# RN4020_Breakout.net
KiCad netlist of a schematic drawn in EAGLE
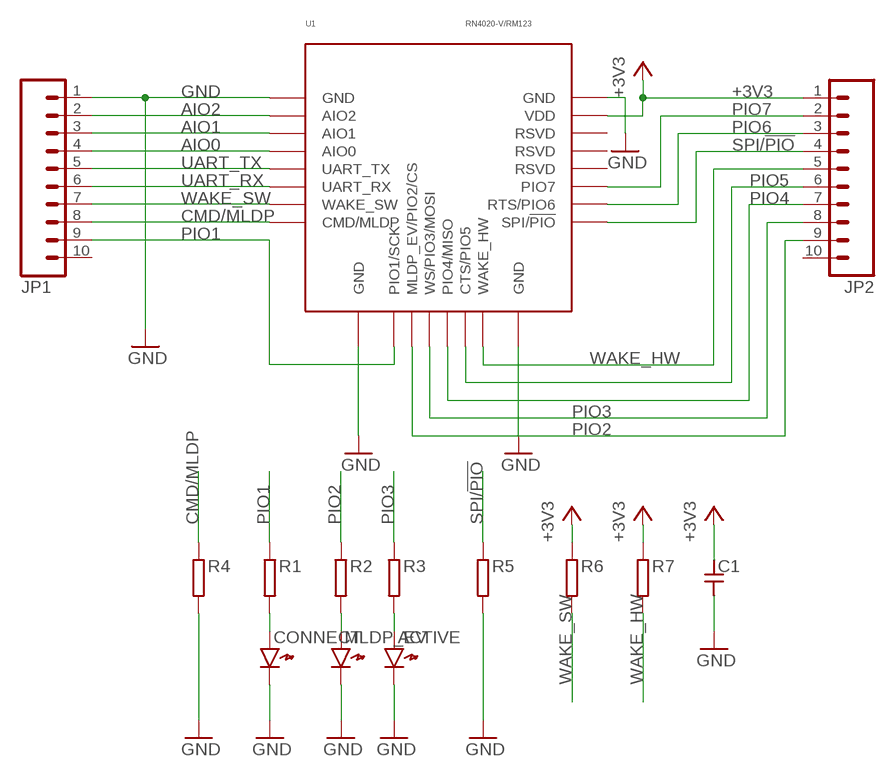
[diagram p0: schematic, sheet 1]

(export (version "E")
  (design (tool "Eeschema 10.0.6"))
  (components
    (comp (ref "ACTIVE")
      (value "LED1608_REDUCED")
      (footprint "eagle-import:LED1608_REDUCED")
      (libsource (lib "eagle-import") (part "LED1608_REDUCED"))
    )
    (comp (ref "C1")
      (value "CAPACITOR1608_REDUCED")
      (footprint "eagle-import:SMD1608_REDUCED")
      (libsource (lib "eagle-import") (part "CAPACITOR1608_REDUCED"))
    )
    (comp (ref "CONNECT")
      (value "LED1608_REDUCED")
      (footprint "eagle-import:LED1608_REDUCED")
      (libsource (lib "eagle-import") (part "LED1608_REDUCED"))
    )
    (comp (ref "JP1")
      (value "M10NOSILK")
      (footprint "eagle-import:1X10-NOSILK")
      (libsource (lib "eagle-import") (part "M10NOSILK"))
    )
    (comp (ref "JP2")
      (value "M10NOSILK")
      (footprint "eagle-import:1X10-NOSILK")
      (libsource (lib "eagle-import") (part "M10NOSILK"))
    )
    (comp (ref "MLDP_EV")
      (value "LED1608_REDUCED")
      (footprint "eagle-import:LED1608_REDUCED")
      (libsource (lib "eagle-import") (part "LED1608_REDUCED"))
    )
    (comp (ref "R1")
      (value "RESISTOR1608_REDUCED")
      (footprint "eagle-import:SMD1608_REDUCED")
      (libsource (lib "eagle-import") (part "RESISTOR1608_REDUCED"))
    )
    (comp (ref "R2")
      (value "RESISTOR1608_REDUCED")
      (footprint "eagle-import:SMD1608_REDUCED")
      (libsource (lib "eagle-import") (part "RESISTOR1608_REDUCED"))
    )
    (comp (ref "R3")
      (value "RESISTOR1608_REDUCED")
      (footprint "eagle-import:SMD1608_REDUCED")
      (libsource (lib "eagle-import") (part "RESISTOR1608_REDUCED"))
    )
    (comp (ref "R4")
      (value "RESISTOR1608_REDUCED")
      (footprint "eagle-import:SMD1608_REDUCED")
      (libsource (lib "eagle-import") (part "RESISTOR1608_REDUCED"))
    )
    (comp (ref "R5")
      (value "RESISTOR1608_REDUCED")
      (footprint "eagle-import:SMD1608_REDUCED")
      (libsource (lib "eagle-import") (part "RESISTOR1608_REDUCED"))
    )
    (comp (ref "R6")
      (value "RESISTOR1608_REDUCED")
      (footprint "eagle-import:SMD1608_REDUCED")
      (libsource (lib "eagle-import") (part "RESISTOR1608_REDUCED"))
    )
    (comp (ref "R7")
      (value "RESISTOR1608_REDUCED")
      (footprint "eagle-import:SMD1608_REDUCED")
      (libsource (lib "eagle-import") (part "RESISTOR1608_REDUCED"))
    )
    (comp (ref "U1")
      (value "RN4020-V/RM123")
      (footprint "eagle-import:RN4020")
      (libsource (lib "eagle-import") (part "RN4020-V/RM123"))
    )
  )
  (nets
    (net (code "1") (name "+3V3") (class "Default")
      (node (ref "C1") (pin "1") (pinfunction "1_1") (pintype "passive"))
      (node (ref "JP2") (pin "1") (pinfunction "1_1") (pintype "passive"))
      (node (ref "R6") (pin "1") (pinfunction "1_1") (pintype "passive"))
      (node (ref "R7") (pin "1") (pinfunction "1_1") (pintype "passive"))
      (node (ref "U1") (pin "23") (pinfunction "VDD_23") (pintype "bidirectional"))
    )
    (net (code "2") (name "/AIO0") (class "Default")
      (node (ref "JP1") (pin "4") (pinfunction "4_4") (pintype "passive"))
      (node (ref "U1") (pin "4") (pinfunction "AIO0_4") (pintype "bidirectional"))
    )
    (net (code "3") (name "/AIO1") (class "Default")
      (node (ref "JP1") (pin "3") (pinfunction "3_3") (pintype "passive"))
      (node (ref "U1") (pin "3") (pinfunction "AIO1_3") (pintype "bidirectional"))
    )
    (net (code "4") (name "/AIO2") (class "Default")
      (node (ref "JP1") (pin "2") (pinfunction "2_2") (pintype "passive"))
      (node (ref "U1") (pin "2") (pinfunction "AIO2_2") (pintype "bidirectional"))
    )
    (net (code "5") (name "/CMD{slash}MLDP") (class "Default")
      (node (ref "JP1") (pin "8") (pinfunction "8_8") (pintype "passive"))
      (node (ref "R4") (pin "1") (pinfunction "1_1") (pintype "passive"))
      (node (ref "U1") (pin "8") (pinfunction "CMD/MLDP_8") (pintype "bidirectional"))
    )
    (net (code "6") (name "/PIO1") (class "Default")
      (node (ref "JP1") (pin "9") (pinfunction "9_9") (pintype "passive"))
      (node (ref "R1") (pin "1") (pinfunction "1_1") (pintype "passive"))
      (node (ref "U1") (pin "10") (pinfunction "PIO1/SCK_10") (pintype "bidirectional"))
    )
    (net (code "7") (name "/PIO2") (class "Default")
      (node (ref "JP2") (pin "9") (pinfunction "9_9") (pintype "passive"))
      (node (ref "R2") (pin "1") (pinfunction "1_1") (pintype "passive"))
      (node (ref "U1") (pin "11") (pinfunction "MLDP_EV/PIO2/CS_11") (pintype "bidirectional"))
    )
    (net (code "8") (name "/PIO3") (class "Default")
      (node (ref "JP2") (pin "8") (pinfunction "8_8") (pintype "passive"))
      (node (ref "R3") (pin "1") (pinfunction "1_1") (pintype "passive"))
      (node (ref "U1") (pin "12") (pinfunction "WS/PIO3/MOSI_12") (pintype "bidirectional"))
    )
    (net (code "9") (name "/PIO4") (class "Default")
      (node (ref "JP2") (pin "7") (pinfunction "7_7") (pintype "passive"))
      (node (ref "U1") (pin "13") (pinfunction "PIO4/MISO_13") (pintype "bidirectional"))
    )
    (net (code "10") (name "/PIO5") (class "Default")
      (node (ref "JP2") (pin "6") (pinfunction "6_6") (pintype "passive"))
      (node (ref "U1") (pin "14") (pinfunction "CTS/PIO5_14") (pintype "bidirectional"))
    )
    (net (code "11") (name "/PIO6") (class "Default")
      (node (ref "JP2") (pin "3") (pinfunction "3_3") (pintype "passive"))
      (node (ref "U1") (pin "18") (pinfunction "RTS/PIO6_18") (pintype "bidirectional"))
    )
    (net (code "12") (name "/PIO7") (class "Default")
      (node (ref "JP2") (pin "2") (pinfunction "2_2") (pintype "passive"))
      (node (ref "U1") (pin "19") (pinfunction "PIO7_19") (pintype "bidirectional"))
    )
    (net (code "13") (name "/SPI{slash}~{PIO}") (class "Default")
      (node (ref "JP2") (pin "4") (pinfunction "4_4") (pintype "passive"))
      (node (ref "R5") (pin "1") (pinfunction "1_1") (pintype "passive"))
      (node (ref "U1") (pin "17") (pinfunction "SPI/~{PIO}_17") (pintype "bidirectional"))
    )
    (net (code "14") (name "/UART_RX") (class "Default")
      (node (ref "JP1") (pin "6") (pinfunction "6_6") (pintype "passive"))
      (node (ref "U1") (pin "6") (pinfunction "UART_RX_6") (pintype "bidirectional"))
    )
    (net (code "15") (name "/UART_TX") (class "Default")
      (node (ref "JP1") (pin "5") (pinfunction "5_5") (pintype "passive"))
      (node (ref "U1") (pin "5") (pinfunction "UART_TX_5") (pintype "bidirectional"))
    )
    (net (code "16") (name "/WAKE_HW") (class "Default")
      (node (ref "JP2") (pin "5") (pinfunction "5_5") (pintype "passive"))
      (node (ref "R7") (pin "2") (pinfunction "2_2") (pintype "passive"))
      (node (ref "U1") (pin "15") (pinfunction "WAKE_HW_15") (pintype "bidirectional"))
    )
    (net (code "17") (name "/WAKE_SW") (class "Default")
      (node (ref "JP1") (pin "7") (pinfunction "7_7") (pintype "passive"))
      (node (ref "R6") (pin "2") (pinfunction "2_2") (pintype "passive"))
      (node (ref "U1") (pin "7") (pinfunction "WAKE_SW_7") (pintype "bidirectional"))
    )
    (net (code "18") (name "GND") (class "Default")
      (node (ref "ACTIVE") (pin "K") (pinfunction "K_K") (pintype "passive"))
      (node (ref "C1") (pin "2") (pinfunction "2_2") (pintype "passive"))
      (node (ref "CONNECT") (pin "K") (pinfunction "K_K") (pintype "passive"))
      (node (ref "JP1") (pin "1") (pinfunction "1_1") (pintype "passive"))
      (node (ref "MLDP_EV") (pin "K") (pinfunction "K_K") (pintype "passive"))
      (node (ref "R4") (pin "2") (pinfunction "2_2") (pintype "passive"))
      (node (ref "R5") (pin "2") (pinfunction "2_2") (pintype "passive"))
      (node (ref "U1") (pin "1") (pinfunction "GND_1") (pintype "bidirectional"))
      (node (ref "U1") (pin "16") (pinfunction "GND_16") (pintype "bidirectional"))
      (node (ref "U1") (pin "24") (pinfunction "GND_24") (pintype "bidirectional"))
      (node (ref "U1") (pin "9") (pinfunction "GND_9") (pintype "bidirectional"))
    )
    (net (code "19") (name "Net-(ACTIVE-PadA)") (class "Default")
      (node (ref "ACTIVE") (pin "A") (pinfunction "A_A") (pintype "passive"))
      (node (ref "R3") (pin "2") (pinfunction "2_2") (pintype "passive"))
    )
    (net (code "20") (name "Net-(CONNECT-PadA)") (class "Default")
      (node (ref "CONNECT") (pin "A") (pinfunction "A_A") (pintype "passive"))
      (node (ref "R1") (pin "2") (pinfunction "2_2") (pintype "passive"))
    )
    (net (code "21") (name "Net-(MLDP_EV-PadA)") (class "Default")
      (node (ref "MLDP_EV") (pin "A") (pinfunction "A_A") (pintype "passive"))
      (node (ref "R2") (pin "2") (pinfunction "2_2") (pintype "passive"))
    )
    (net (code "22") (name "unconnected-(JP1-Pad10)") (class "Default")
      (node (ref "JP1") (pin "10") (pinfunction "10_10") (pintype "passive"))
    )
    (net (code "23") (name "unconnected-(JP2-Pad10)") (class "Default")
      (node (ref "JP2") (pin "10") (pinfunction "10_10") (pintype "passive"))
    )
    (net (code "24") (name "unconnected-(U1-RSVD-Pad20)") (class "Default")
      (node (ref "U1") (pin "20") (pinfunction "RSVD_20") (pintype "bidirectional"))
    )
    (net (code "25") (name "unconnected-(U1-RSVD-Pad21)") (class "Default")
      (node (ref "U1") (pin "21") (pinfunction "RSVD_21") (pintype "bidirectional"))
    )
    (net (code "26") (name "unconnected-(U1-RSVD-Pad22)") (class "Default")
      (node (ref "U1") (pin "22") (pinfunction "RSVD_22") (pintype "bidirectional"))
    )
  )
)
